# INC_enc_driver.net
KiCad netlist of a schematic drawn in Altium Designer
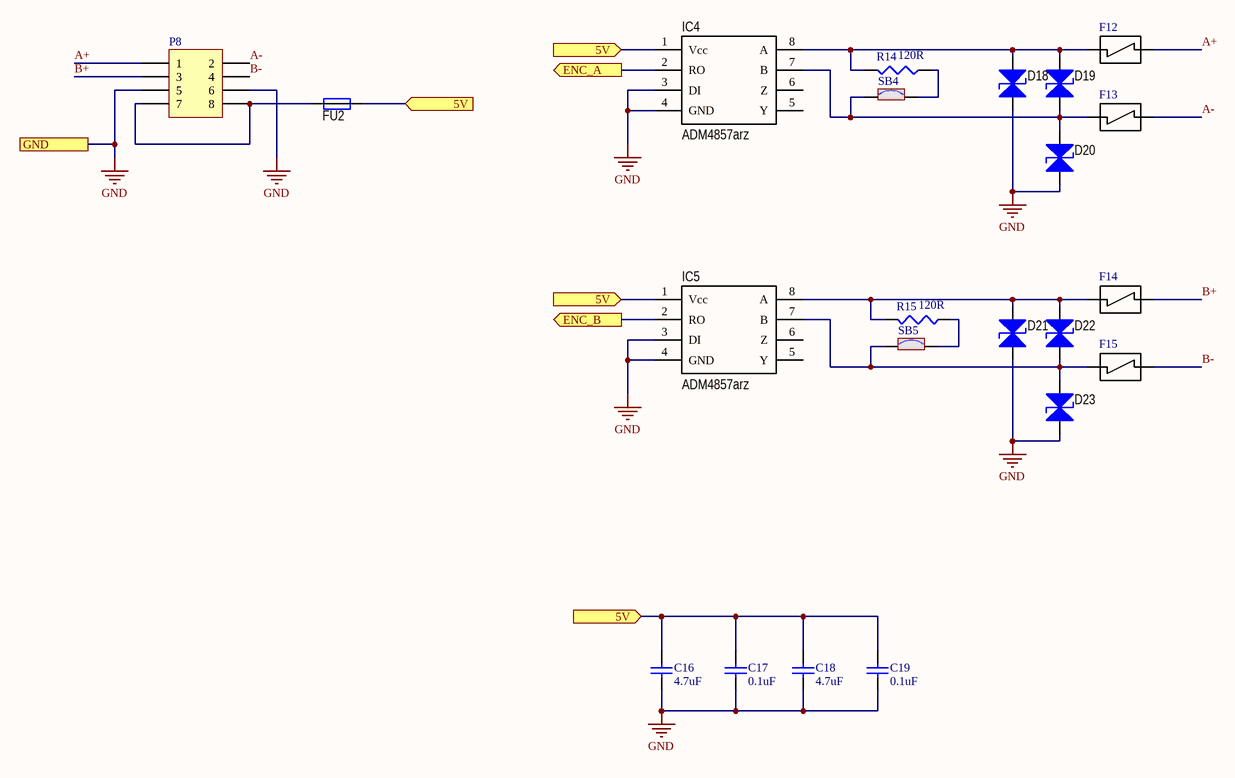
[diagram p0: INC_enc_driver.SchDoc]

(export (version "E")
  (design (tool "Eeschema 10.0.6"))
  (components
    (comp (ref "C16")
      (value "4.7uF")
      (footprint "C1608-0603")
      (description "Керамическийконденсатор")
      (libsource (lib "db") (part "Cap"))
    )
    (comp (ref "C17")
      (value "0.1uF")
      (footprint "C1608-0603")
      (description "Керамическийконденсатор")
      (libsource (lib "db") (part "Cap"))
    )
    (comp (ref "C18")
      (value "4.7uF")
      (footprint "C1608-0603")
      (description "Керамическийконденсатор")
      (libsource (lib "db") (part "Cap"))
    )
    (comp (ref "C19")
      (value "0.1uF")
      (footprint "C1608-0603")
      (description "Керамическийконденсатор")
      (libsource (lib "db") (part "Cap"))
    )
    (comp (ref "D18")
      (value "SMBJ5.0CA")
      (footprint "SMB_H")
      (description "Супрессор двунаправленный")
      (libsource (lib "db") (part "SMBJ_CА"))
    )
    (comp (ref "D19")
      (value "SMBJ5.0CA")
      (footprint "SMB_H")
      (description "Супрессор двунаправленный")
      (libsource (lib "db") (part "SMBJ_CА"))
    )
    (comp (ref "D20")
      (value "SMBJ5.0CA")
      (footprint "SMB_H")
      (description "Супрессор двунаправленный")
      (libsource (lib "db") (part "SMBJ_CА"))
    )
    (comp (ref "D21")
      (value "SMBJ5.0CA")
      (footprint "SMB_H")
      (description "Супрессор двунаправленный")
      (libsource (lib "db") (part "SMBJ_CА"))
    )
    (comp (ref "D22")
      (value "SMBJ5.0CA")
      (footprint "SMB_H")
      (description "Супрессор двунаправленный")
      (libsource (lib "db") (part "SMBJ_CА"))
    )
    (comp (ref "D23")
      (value "SMBJ5.0CA")
      (footprint "SMB_H")
      (description "Супрессор двунаправленный")
      (libsource (lib "db") (part "SMBJ_CА"))
    )
    (comp (ref "F12")
      (value "TBU-CA065-200-WH")
      (footprint "TBU_CA")
      (description "Самовосстанавливающийся предохранитель")
      (libsource (lib "db") (part "TBU-CA"))
    )
    (comp (ref "F13")
      (value "TBU-CA065-200-WH")
      (footprint "TBU_CA")
      (description "Самовосстанавливающийся предохранитель")
      (libsource (lib "db") (part "TBU-CA"))
    )
    (comp (ref "F14")
      (value "TBU-CA065-200-WH")
      (footprint "TBU_CA")
      (description "Самовосстанавливающийся предохранитель")
      (libsource (lib "db") (part "TBU-CA"))
    )
    (comp (ref "F15")
      (value "TBU-CA065-200-WH")
      (footprint "TBU_CA")
      (description "Самовосстанавливающийся предохранитель")
      (libsource (lib "db") (part "TBU-CA"))
    )
    (comp (ref "FU2")
      (value "MF-MSMF030")
      (footprint "MF-MSMF")
      (description "PTC Resettable Fuses")
      (libsource (lib "db") (part "MF-MSMF030"))
    )
    (comp (ref "IC4")
      (value "ADM4857arz")
      (footprint "SO8_N")
      (description "RS-485 Трансивер")
      (libsource (lib "db") (part "ADM4857"))
    )
    (comp (ref "IC5")
      (value "ADM4857arz")
      (footprint "SO8_N")
      (description "RS-485 Трансивер")
      (libsource (lib "db") (part "ADM4857"))
    )
    (comp (ref "P8")
      (value "BH-08")
      (footprint "BH-08")
      (description "Разъем штыревой на плату")
      (libsource (lib "db") (part "BH-08"))
    )
    (comp (ref "R14")
      (value "120R")
      (footprint "R1608-0603")
      (description "SMD резистор")
      (libsource (lib "db") (part "resistor"))
    )
    (comp (ref "R15")
      (value "120R")
      (footprint "R1608-0603")
      (description "SMD резистор")
      (libsource (lib "db") (part "resistor"))
    )
    (comp (ref "SB4")
      (value "~")
      (footprint "SOLDER-BRIDGE_R0603-0R")
      (description "Перемычка")
      (libsource (lib "db") (part "SB"))
    )
    (comp (ref "SB5")
      (value "~")
      (footprint "SOLDER-BRIDGE_R0603-0R")
      (description "Перемычка")
      (libsource (lib "db") (part "SB"))
    )
  )
  (nets
    (net (code "1") (name "/5V") (class "Default")
      (node (ref "C16") (pin "2") (pinfunction "2_2") (pintype "passive"))
      (node (ref "C17") (pin "2") (pinfunction "2_2") (pintype "passive"))
      (node (ref "C18") (pin "2") (pinfunction "2_2") (pintype "passive"))
      (node (ref "C19") (pin "2") (pinfunction "2_2") (pintype "passive"))
      (node (ref "FU2") (pin "2") (pinfunction "2_2") (pintype "passive"))
      (node (ref "IC4") (pin "1") (pinfunction "Vcc_1") (pintype "passive"))
      (node (ref "IC5") (pin "1") (pinfunction "Vcc_1") (pintype "passive"))
    )
    (net (code "2") (name "/A+") (class "Default")
      (node (ref "F12") (pin "1") (pintype "passive"))
      (node (ref "P8") (pin "1") (pinfunction "1_1") (pintype "passive"))
    )
    (net (code "3") (name "/A-") (class "Default")
      (node (ref "F13") (pin "1") (pintype "passive"))
      (node (ref "P8") (pin "2") (pinfunction "2_2") (pintype "passive"))
    )
    (net (code "4") (name "/B+") (class "Default")
      (node (ref "F14") (pin "1") (pintype "passive"))
      (node (ref "P8") (pin "3") (pinfunction "3_3") (pintype "passive"))
    )
    (net (code "5") (name "/B-") (class "Default")
      (node (ref "F15") (pin "1") (pintype "passive"))
      (node (ref "P8") (pin "4") (pinfunction "4_4") (pintype "passive"))
    )
    (net (code "6") (name "/ENC_A") (class "Default")
      (node (ref "IC4") (pin "2") (pinfunction "RO_2") (pintype "power_in"))
    )
    (net (code "7") (name "/ENC_B") (class "Default")
      (node (ref "IC5") (pin "2") (pinfunction "RO_2") (pintype "power_in"))
    )
    (net (code "8") (name "GND") (class "Default")
      (node (ref "C16") (pin "1") (pinfunction "1_1") (pintype "passive"))
      (node (ref "C17") (pin "1") (pinfunction "1_1") (pintype "passive"))
      (node (ref "C18") (pin "1") (pinfunction "1_1") (pintype "passive"))
      (node (ref "C19") (pin "1") (pinfunction "1_1") (pintype "passive"))
      (node (ref "D18") (pin "1") (pinfunction "K_1") (pintype "passive"))
      (node (ref "D20") (pin "1") (pinfunction "K_1") (pintype "passive"))
      (node (ref "D21") (pin "1") (pinfunction "K_1") (pintype "passive"))
      (node (ref "D23") (pin "1") (pinfunction "K_1") (pintype "passive"))
      (node (ref "IC4") (pin "3") (pinfunction "DI_3") (pintype "passive"))
      (node (ref "IC4") (pin "4") (pinfunction "GND_4") (pintype "passive"))
      (node (ref "IC5") (pin "3") (pinfunction "DI_3") (pintype "passive"))
      (node (ref "IC5") (pin "4") (pinfunction "GND_4") (pintype "passive"))
      (node (ref "P8") (pin "5") (pinfunction "5_5") (pintype "passive"))
      (node (ref "P8") (pin "6") (pinfunction "6_6") (pintype "passive"))
    )
    (net (code "9") (name "Net-(D18-A)") (class "Default")
      (node (ref "D18") (pin "2") (pinfunction "A_2") (pintype "passive"))
      (node (ref "D19") (pin "2") (pinfunction "A_2") (pintype "passive"))
      (node (ref "F12") (pin "0") (pintype "passive"))
      (node (ref "IC4") (pin "8") (pinfunction "A_8") (pintype "passive"))
      (node (ref "R14") (pin "2") (pinfunction "2_2") (pintype "passive"))
    )
    (net (code "10") (name "Net-(D19-K)") (class "Default")
      (node (ref "D19") (pin "1") (pinfunction "K_1") (pintype "passive"))
      (node (ref "D20") (pin "2") (pinfunction "A_2") (pintype "passive"))
      (node (ref "F13") (pin "0") (pintype "passive"))
      (node (ref "IC4") (pin "7") (pinfunction "B_7") (pintype "passive"))
      (node (ref "SB4") (pin "1") (pinfunction "1_1") (pintype "passive"))
    )
    (net (code "11") (name "Net-(D21-A)") (class "Default")
      (node (ref "D21") (pin "2") (pinfunction "A_2") (pintype "passive"))
      (node (ref "D22") (pin "2") (pinfunction "A_2") (pintype "passive"))
      (node (ref "F14") (pin "0") (pintype "passive"))
      (node (ref "IC5") (pin "8") (pinfunction "A_8") (pintype "passive"))
      (node (ref "R15") (pin "2") (pinfunction "2_2") (pintype "passive"))
    )
    (net (code "12") (name "Net-(D22-K)") (class "Default")
      (node (ref "D22") (pin "1") (pinfunction "K_1") (pintype "passive"))
      (node (ref "D23") (pin "2") (pinfunction "A_2") (pintype "passive"))
      (node (ref "F15") (pin "0") (pintype "passive"))
      (node (ref "IC5") (pin "7") (pinfunction "B_7") (pintype "passive"))
      (node (ref "SB5") (pin "1") (pinfunction "1_1") (pintype "passive"))
    )
    (net (code "13") (name "Net-(FU2-Pad1)") (class "Default")
      (node (ref "FU2") (pin "1") (pinfunction "1_1") (pintype "passive"))
      (node (ref "P8") (pin "7") (pinfunction "7_7") (pintype "passive"))
      (node (ref "P8") (pin "8") (pinfunction "8_8") (pintype "passive"))
    )
    (net (code "14") (name "Net-(R14-Pad1)") (class "Default")
      (node (ref "R14") (pin "1") (pinfunction "1_1") (pintype "passive"))
      (node (ref "SB4") (pin "2") (pinfunction "2_2") (pintype "passive"))
    )
    (net (code "15") (name "Net-(R15-Pad1)") (class "Default")
      (node (ref "R15") (pin "1") (pinfunction "1_1") (pintype "passive"))
      (node (ref "SB5") (pin "2") (pinfunction "2_2") (pintype "passive"))
    )
    (net (code "16") (name "unconnected-(IC4-Y-Pad5)") (class "Default")
      (node (ref "IC4") (pin "5") (pinfunction "Y_5") (pintype "passive"))
    )
    (net (code "17") (name "unconnected-(IC4-Z-Pad6)") (class "Default")
      (node (ref "IC4") (pin "6") (pinfunction "Z_6") (pintype "power_in"))
    )
    (net (code "18") (name "unconnected-(IC5-Y-Pad5)") (class "Default")
      (node (ref "IC5") (pin "5") (pinfunction "Y_5") (pintype "passive"))
    )
    (net (code "19") (name "unconnected-(IC5-Z-Pad6)") (class "Default")
      (node (ref "IC5") (pin "6") (pinfunction "Z_6") (pintype "power_in"))
    )
  )
)
